# 3_3V_Regulator.net
KiCad netlist of a schematic drawn in Altium Designer
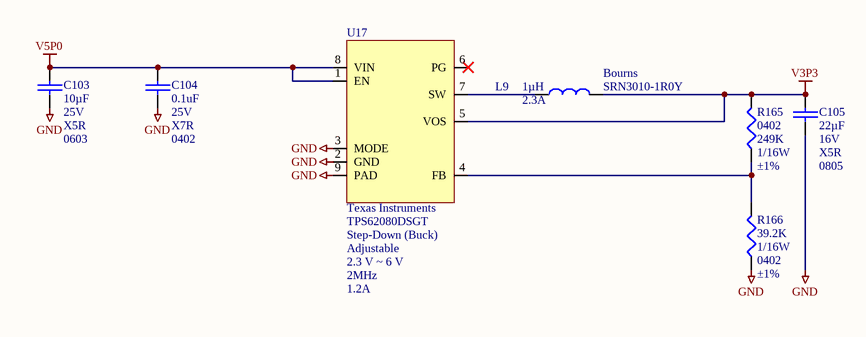
[diagram p0: 3.3V Regulator.SchDoc]

(export (version "E")
  (design (tool "Eeschema 10.0.6"))
  (components
    (comp (ref "C103")
      (value "C_0603_10µF")
      (footprint "C_ERA-0603")
      (description "CAP CER 10UF 16V X5R 0603")
      (fields
        (field (name "CAPACITANCE") "10µF")
        (field (name "VOLTAGE - RATED") "25V")
        (field (name "TEMPERATURE COEFFICIENT") "X5R")
        (field (name "PACKAGE / CASE") "0603")
        (field (name "MANUFACTURER") "Murata Electronics North America")
        (field (name "MANUFACTURER PART NUMBER") "GRM188R61C106MA73D")
      )
      (libsource (lib "Cospan Design") (part "C_0603_10µF"))
    )
    (comp (ref "C104")
      (value "C_0402_0.1UF_25V")
      (footprint "C_0402")
      (description "CAP CER 0.1UF 25V X6S 0402")
      (fields
        (field (name "TOLERANCE") "10%")
        (field (name "CAPACITANCE") "0.1uF")
        (field (name "VOLTAGE - RATED") "25V")
        (field (name "TEMPERATURE COEFFICIENT") "X7R")
        (field (name "PACKAGE / CASE") "0402")
      )
      (libsource (lib "Cospan Design") (part "C_0402_0.1UF_25V"))
    )
    (comp (ref "C105")
      (value "22µF")
      (footprint "C_0805")
      (description "CAP CER 22UF 16V 10% X5R 0805")
      (fields
        (field (name "TOLERANCE") "20%")
        (field (name "CAPACITANCE") "22µF")
        (field (name "VOLTAGE - RATED") "16V")
        (field (name "TEMPERATURE COEFFICIENT") "X5R")
        (field (name "PACKAGE / CASE") "0805")
      )
      (libsource (lib "Main Library") (part "C_0805_22µF_16V"))
    )
    (comp (ref "L9")
      (value "1.0uH")
      (footprint "SRN3010-1R0Y")
      (description "FIXED IND 1UH 2.3A 63 MOHM SMD")
      (fields
        (field (name "TOLERANCE") "30%")
        (field (name "DC CURRENT") "2.3A")
        (field (name "INDUCTANCE") "1µH")
        (field (name "MANUFACTURER 1") "Bourns")
        (field (name "MANUFACTURER PART NUMBER 1") "SRN3010-1R0Y")
      )
      (libsource (lib "Main Library") (part "L_1.0UH_2.3A"))
    )
    (comp (ref "R165")
      (value "R_0402_249K")
      (footprint "R_0402")
      (description "RES 249K OHM 1/16W 1% 0402 SMD")
      (fields
        (field (name "MANUFACTURER") "Yageo")
        (field (name "MANUFACTURER PART NUMBER") "RC0402FR-07249KL")
        (field (name "PACKAGE / CASE") "0402")
        (field (name "RESISTANCE (OHMS)") "249K")
        (field (name "POWER (WATTS)") "1/16W")
        (field (name "TOLERANCE") "±1%")
      )
      (libsource (lib "Main Library") (part "R_0402_249K"))
    )
    (comp (ref "R166")
      (value "R_0402_39.2K")
      (footprint "R_0402")
      (description "RES 39.2K OHM 1/16W 1% 0402 SMD")
      (fields
        (field (name "MANUFACTURER") "Yageo")
        (field (name "MANUFACTURER PART NUMBER") "RC0402FR-0739K2L")
        (field (name "RESISTANCE IN OHMS") "39.2K")
        (field (name "POWER (WATTS)") "1/16W")
        (field (name "CASE") "0402")
        (field (name "TOLERANCE") "±1%")
      )
      (libsource (lib "Main Library") (part "R_0402_39.2K"))
    )
    (comp (ref "U17")
      (value "TPS62080")
      (footprint "QFN50P200X200X80-8L")
      (description "IC BUCK SYNC ADJ 1.2A 8WSON")
      (fields
        (field (name "MANUFACTURER") "Texas Instruments")
        (field (name "MANUFACTURER PART NUMBER") "TPS62080DSGT")
        (field (name "TYPE") "Step-Down (Buck)")
        (field (name "OUTPUT TYPE") "Adjustable")
        (field (name "VOLTAGE - INPUT") "2.3 V ~ 6 V")
        (field (name "FREQUENCY - SWITCHING") "2MHz")
        (field (name "CURRENT - OUTPUT") "1.2A")
      )
      (libsource (lib "Main Library") (part "U_TPS62080"))
    )
  )
  (nets
    (net (code "1") (name "GND") (class "Default")
      (node (ref "C103") (pin "1") (pinfunction "1_1") (pintype "passive"))
      (node (ref "C104") (pin "1") (pinfunction "1_1") (pintype "passive"))
      (node (ref "C105") (pin "1") (pinfunction "1_1") (pintype "passive"))
      (node (ref "R166") (pin "2") (pinfunction "2_2") (pintype "passive"))
      (node (ref "U17") (pin "2") (pinfunction "GND_2") (pintype "passive"))
      (node (ref "U17") (pin "3") (pinfunction "MODE_3") (pintype "passive"))
      (node (ref "U17") (pin "9") (pinfunction "PAD_9") (pintype "passive"))
    )
    (net (code "2") (name "Net-(U17-FB)") (class "Default")
      (node (ref "R165") (pin "2") (pinfunction "2_2") (pintype "passive"))
      (node (ref "R166") (pin "1") (pinfunction "1_1") (pintype "passive"))
      (node (ref "U17") (pin "4") (pinfunction "FB_4") (pintype "passive"))
    )
    (net (code "3") (name "Net-(U17-SW)") (class "Default")
      (node (ref "L9") (pin "1") (pintype "passive"))
      (node (ref "U17") (pin "7") (pinfunction "SW_7") (pintype "passive"))
    )
    (net (code "4") (name "V3P3") (class "Default")
      (node (ref "C105") (pin "2") (pinfunction "2_2") (pintype "passive"))
      (node (ref "L9") (pin "2") (pintype "passive"))
      (node (ref "R165") (pin "1") (pinfunction "1_1") (pintype "passive"))
      (node (ref "U17") (pin "5") (pinfunction "VOS_5") (pintype "passive"))
    )
    (net (code "5") (name "V5P0") (class "Default")
      (node (ref "C103") (pin "2") (pinfunction "2_2") (pintype "passive"))
      (node (ref "C104") (pin "2") (pinfunction "2_2") (pintype "passive"))
      (node (ref "U17") (pin "1") (pinfunction "EN_1") (pintype "passive"))
      (node (ref "U17") (pin "8") (pinfunction "VIN_8") (pintype "passive"))
    )
    (net (code "6") (name "unconnected-(U17-PG-Pad6)") (class "Default")
      (node (ref "U17") (pin "6") (pinfunction "PG_6") (pintype "passive+no_connect"))
    )
  )
)
